# nfc-epd-afe.net
KiCad netlist of a schematic drawn in Altium Designer
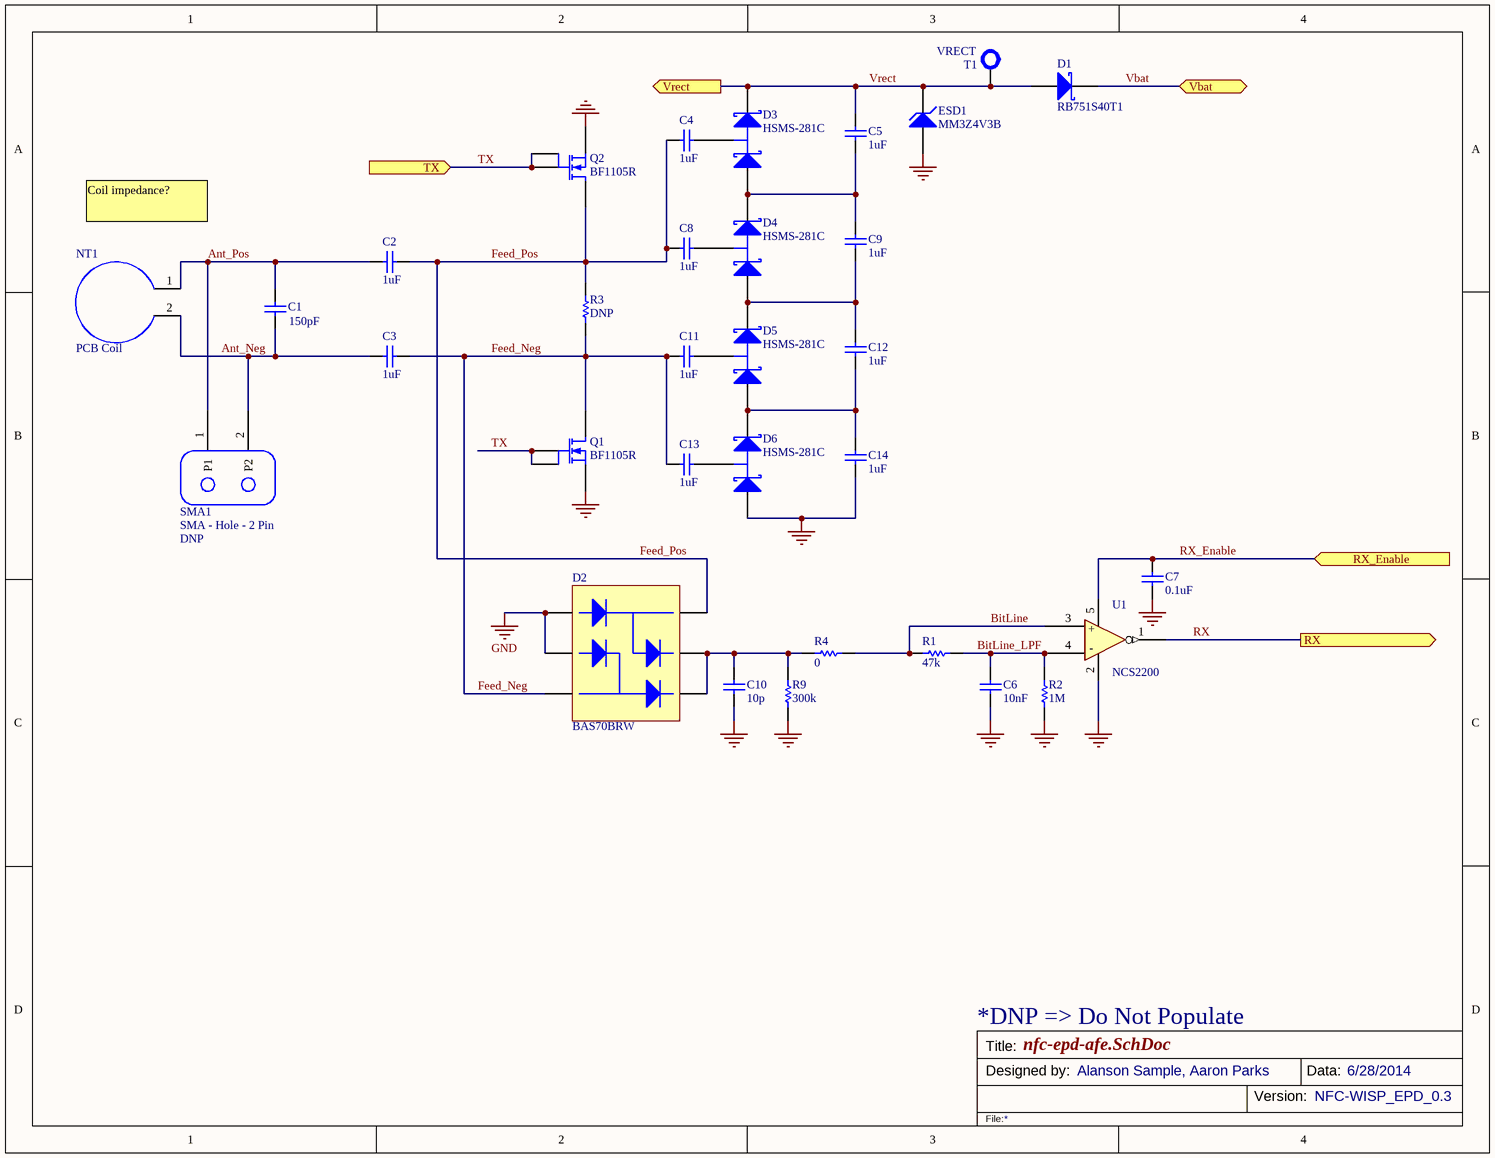
[diagram p0: nfc-epd-afe.SchDoc]

(export (version "E")
  (design (tool "Eeschema 10.0.6"))
  (components
    (comp (ref "C1")
      (value "150pF")
      (footprint "0603")
      (description "Ceramic Capacitor (Surface Mount)")
      (fields (field (name "MANUFACTURER") "Generic Ceramic Chip Cap (TBD)") (field (name "Comment") "Cap"))
      (libsource (lib "WISP_AD10") (part "Cap"))
    )
    (comp (ref "C2")
      (value "1uF")
      (footprint "0402")
      (description "Ceramic Capacitor (Surface Mount)")
      (fields (field (name "MANUFACTURER") "Generic Ceramic Chip Cap (TBD)") (field (name "Comment") "Cap"))
      (libsource (lib "WISP_AD10") (part "Cap"))
    )
    (comp (ref "C3")
      (value "1uF")
      (footprint "0402")
      (description "Ceramic Capacitor (Surface Mount)")
      (fields (field (name "MANUFACTURER") "Generic Ceramic Chip Cap (TBD)") (field (name "Comment") "Cap"))
      (libsource (lib "WISP_AD10") (part "Cap"))
    )
    (comp (ref "C4")
      (value "1uF")
      (footprint "0402")
      (description "Ceramic Capacitor (Surface Mount)")
      (fields (field (name "MANUFACTURER") "Generic Ceramic Chip Cap (TBD)") (field (name "Comment") "Cap"))
      (libsource (lib "WISP_AD10") (part "Cap"))
    )
    (comp (ref "C5")
      (value "1uF")
      (footprint "0402")
      (description "Ceramic Capacitor (Surface Mount)")
      (fields (field (name "MANUFACTURER") "Generic Ceramic Chip Cap (TBD)") (field (name "Comment") "Cap"))
      (libsource (lib "WISP_AD10") (part "Cap"))
    )
    (comp (ref "C6")
      (value "10nF")
      (footprint "0402")
      (description "Ceramic Capacitor (Surface Mount)")
      (fields (field (name "MANUFACTURER") "Generic Ceramic Chip Cap (TBD)") (field (name "Comment") "Cap"))
      (libsource (lib "WISP_AD10") (part "Cap"))
    )
    (comp (ref "C7")
      (value "0.1uF")
      (footprint "0402")
      (description "Ceramic Capacitor (Surface Mount)")
      (fields (field (name "MANUFACTURER") "Generic Ceramic Chip Cap (TBD)") (field (name "Comment") "Cap"))
      (libsource (lib "WISP_AD10") (part "Cap"))
    )
    (comp (ref "C8")
      (value "1uF")
      (footprint "0402")
      (description "Ceramic Capacitor (Surface Mount)")
      (fields (field (name "MANUFACTURER") "Generic Ceramic Chip Cap (TBD)") (field (name "Comment") "Cap"))
      (libsource (lib "WISP_AD10") (part "Cap"))
    )
    (comp (ref "C9")
      (value "1uF")
      (footprint "0402")
      (description "Ceramic Capacitor (Surface Mount)")
      (fields (field (name "MANUFACTURER") "Generic Ceramic Chip Cap (TBD)") (field (name "Comment") "Cap"))
      (libsource (lib "WISP_AD10") (part "Cap"))
    )
    (comp (ref "C10")
      (value "10p")
      (footprint "0402")
      (description "Ceramic Capacitor (Surface Mount)")
      (fields (field (name "MANUFACTURER") "Generic Ceramic Chip Cap (TBD)") (field (name "Comment") "Cap"))
      (libsource (lib "WISP_AD10") (part "Cap"))
    )
    (comp (ref "C11")
      (value "1uF")
      (footprint "0402")
      (description "Ceramic Capacitor (Surface Mount)")
      (fields (field (name "MANUFACTURER") "Generic Ceramic Chip Cap (TBD)") (field (name "Comment") "Cap"))
      (libsource (lib "WISP_AD10") (part "Cap"))
    )
    (comp (ref "C12")
      (value "1uF")
      (footprint "0402")
      (description "Ceramic Capacitor (Surface Mount)")
      (fields (field (name "MANUFACTURER") "Generic Ceramic Chip Cap (TBD)") (field (name "Comment") "Cap"))
      (libsource (lib "WISP_AD10") (part "Cap"))
    )
    (comp (ref "C13")
      (value "1uF")
      (footprint "0402")
      (description "Ceramic Capacitor (Surface Mount)")
      (fields (field (name "MANUFACTURER") "Generic Ceramic Chip Cap (TBD)") (field (name "Comment") "Cap"))
      (libsource (lib "WISP_AD10") (part "Cap"))
    )
    (comp (ref "C14")
      (value "1uF")
      (footprint "0402")
      (description "Ceramic Capacitor (Surface Mount)")
      (fields (field (name "MANUFACTURER") "Generic Ceramic Chip Cap (TBD)") (field (name "Comment") "Cap"))
      (libsource (lib "WISP_AD10") (part "Cap"))
    )
    (comp (ref "D1")
      (value "RB751S40T1")
      (footprint "SOD-523")
      (description "Schottky Diode")
      (fields (field (name "PUBLISHER") "Altium Limited"))
      (libsource (lib "WISP_AD10") (part "RB751S40T1"))
    )
    (comp (ref "D2")
      (value "BAS70BRW")
      (footprint "SOT-363")
      (description "Diode Array - 2 Pair Series Connection")
      (fields
        (field (name "MANUFACTURER") "Diodes Inc")
        (field (name "MANUFACTURER PART NUMBER") "BAS70BRW-7-F")
      )
      (libsource (lib "WISP_AD10") (part "Diode - Array_2"))
    )
    (comp (ref "D3")
      (value "HSMS-281C")
      (footprint "SOT-323, HSMS-285C")
      (description "Agilent Schottky Diode, Two in Series, Small Package SOT-323")
      (fields
        (field (name "DIGI-KEY PART NUMBER") "*not stocked")
        (field (name "MANUFACTURER") "Avago Technologies US Inc.")
      )
      (libsource (lib "WISP_AD10") (part "HSMS-281C"))
    )
    (comp (ref "D4")
      (value "HSMS-281C")
      (footprint "SOT-323, HSMS-285C")
      (description "Agilent Schottky Diode, Two in Series, Small Package SOT-323")
      (fields
        (field (name "DIGI-KEY PART NUMBER") "*not stocked")
        (field (name "MANUFACTURER") "Avago Technologies US Inc.")
      )
      (libsource (lib "WISP_AD10") (part "HSMS-281C"))
    )
    (comp (ref "D5")
      (value "HSMS-281C")
      (footprint "SOT-323, HSMS-285C")
      (description "Agilent Schottky Diode, Two in Series, Small Package SOT-323")
      (fields
        (field (name "DIGI-KEY PART NUMBER") "*not stocked")
        (field (name "MANUFACTURER") "Avago Technologies US Inc.")
      )
      (libsource (lib "WISP_AD10") (part "HSMS-281C"))
    )
    (comp (ref "D6")
      (value "HSMS-281C")
      (footprint "SOT-323, HSMS-285C")
      (description "Agilent Schottky Diode, Two in Series, Small Package SOT-323")
      (fields
        (field (name "DIGI-KEY PART NUMBER") "*not stocked")
        (field (name "MANUFACTURER") "Avago Technologies US Inc.")
      )
      (libsource (lib "WISP_AD10") (part "HSMS-281C"))
    )
    (comp (ref "ESD1")
      (value "MM3Z4V3B")
      (footprint "SOD-323")
      (description "Vz=4.3V, Overvoltage Protection Zener")
      (fields (field (name "MANUFACTURER") "Fairchild") (field (name "DIGI-KEY PART NUMBER") "MM3Z4V3BCT-ND"))
      (libsource (lib "WISP_AD10") (part "MM3Z4V3B"))
    )
    (comp (ref "NT1")
      (value "PCB Coil")
      (footprint "Net Tie - 20mil")
      (description "Hand draw coil symbol based on a 'Net Tie'")
      (libsource (lib "WISP_AD10") (part "Net Tie - Coil"))
    )
    (comp (ref "Q1")
      (value "BF1105R")
      (footprint "SOT-143R")
      (description "SOT-143R, N-Channel Dual-Gate Mos-Fets MOSFET")
      (fields
        (field (name "DIGI-KEY PART NUMBER") "BF1105R,215-ND")
        (field (name "MANUFACTURER PART NUMBER") "BF1105R,215")
      )
      (libsource (lib "WISP_AD10") (part "BF1105R"))
    )
    (comp (ref "Q2")
      (value "BF1105R")
      (footprint "SOT-143R")
      (description "SOT-143R, N-Channel Dual-Gate Mos-Fets MOSFET")
      (fields
        (field (name "DIGI-KEY PART NUMBER") "BF1105R,215-ND")
        (field (name "MANUFACTURER PART NUMBER") "BF1105R,215")
      )
      (libsource (lib "WISP_AD10") (part "BF1105R"))
    )
    (comp (ref "R1")
      (value "47k")
      (footprint "0402")
      (description "Chip Resistor (Surface Mount)")
      (fields (field (name "MANUFACTURER") "Generic Chip Res (TBD)") (field (name "Comment") "Res"))
      (libsource (lib "WISP_AD10") (part "Res"))
    )
    (comp (ref "R2")
      (value "1M")
      (footprint "0402")
      (description "Chip Resistor (Surface Mount)")
      (fields (field (name "MANUFACTURER") "Generic Chip Res (TBD)") (field (name "Comment") "Res"))
      (libsource (lib "WISP_AD10") (part "Res"))
    )
    (comp (ref "R3")
      (value "DNP")
      (footprint "0402")
      (description "Chip Resistor (Surface Mount)")
      (fields (field (name "MANUFACTURER") "Generic Chip Res (TBD)") (field (name "Comment") "Res"))
      (libsource (lib "WISP_AD10") (part "Res"))
    )
    (comp (ref "R4")
      (value "0")
      (footprint "0402")
      (description "Chip Resistor (Surface Mount)")
      (fields (field (name "MANUFACTURER") "Generic Chip Res (TBD)") (field (name "Comment") "Res"))
      (libsource (lib "WISP_AD10") (part "Res"))
    )
    (comp (ref "R9")
      (value "300k")
      (footprint "0402")
      (description "Chip Resistor (Surface Mount)")
      (fields (field (name "MANUFACTURER") "Generic Chip Res (TBD)") (field (name "Comment") "Res"))
      (libsource (lib "WISP_AD10") (part "Res"))
    )
    (comp (ref "SMA1")
      (value "SMA - Hole - 2 Pin")
      (footprint "SMA - Hole - 2 Pin")
      (description "Two pin SMA connector wisp")
      (fields (field (name "NOTE") "DNP"))
      (libsource (lib "WISP_AD10") (part "SMA - Hole - 2 Pin"))
    )
    (comp (ref "T1")
      (value "Test Point")
      (footprint "Test Point - Super Small")
      (description "Test Point, large or small foot prints")
      (fields
        (field (name "DIGI-KEY PART NUMBER") "Example: 5000K-ND, 5012K-ND, Surface mount 5015KCT-ND")
        (field (name "MANUFACTURER PART NUMBER") "Example: 5000, 5013")
        (field (name "NOTE") "VRECT")
      )
      (libsource (lib "WISP_AD10") (part "Test Point"))
    )
    (comp (ref "U1")
      (value "NCS2200")
      (footprint "SC70-5")
      (description "Comparator: On Semi 10uA Comparator")
      (fields
        (field (name "DIGI-KEY PART NUMBER") "NCS2200SQ2T2GOSTR-ND")
        (field (name "MANUFACTURER") "ON Semiconductor")
      )
      (libsource (lib "WISP_AD10") (part "NCS2200"))
    )
  )
  (nets
    (net (code "1") (name "/Ant_Neg") (class "Default")
      (node (ref "C1") (pin "2") (pinfunction "2_2") (pintype "passive"))
      (node (ref "C3") (pin "1") (pinfunction "1_1") (pintype "passive"))
      (node (ref "NT1") (pin "2") (pinfunction "N2_2") (pintype "passive"))
      (node (ref "SMA1") (pin "2") (pinfunction "P2_2") (pintype "passive"))
    )
    (net (code "2") (name "/Ant_Pos") (class "Default")
      (node (ref "C1") (pin "1") (pinfunction "1_1") (pintype "passive"))
      (node (ref "C2") (pin "1") (pinfunction "1_1") (pintype "passive"))
      (node (ref "NT1") (pin "1") (pinfunction "N1_1") (pintype "passive"))
      (node (ref "SMA1") (pin "1") (pinfunction "P1_1") (pintype "passive"))
    )
    (net (code "3") (name "/BitLine") (class "Default")
      (node (ref "R1") (pin "1") (pinfunction "1_1") (pintype "passive"))
      (node (ref "R4") (pin "2") (pinfunction "2_2") (pintype "passive"))
      (node (ref "U1") (pin "3") (pinfunction "IN+_3") (pintype "passive"))
    )
    (net (code "4") (name "/BitLine_LPF") (class "Default")
      (node (ref "C6") (pin "1") (pinfunction "1_1") (pintype "passive"))
      (node (ref "R1") (pin "2") (pinfunction "2_2") (pintype "passive"))
      (node (ref "R2") (pin "1") (pinfunction "1_1") (pintype "passive"))
      (node (ref "U1") (pin "4") (pinfunction "In-_4") (pintype "passive"))
    )
    (net (code "5") (name "/Feed_Neg") (class "Default")
      (node (ref "C11") (pin "1") (pinfunction "1_1") (pintype "passive"))
      (node (ref "C13") (pin "1") (pinfunction "1_1") (pintype "passive"))
      (node (ref "C3") (pin "2") (pinfunction "2_2") (pintype "passive"))
      (node (ref "D2") (pin "3") (pinfunction "AC2_3") (pintype "passive"))
      (node (ref "Q1") (pin "2") (pinfunction "D_2") (pintype "passive"))
      (node (ref "R3") (pin "2") (pinfunction "2_2") (pintype "passive"))
    )
    (net (code "6") (name "/Feed_Pos") (class "Default")
      (node (ref "C2") (pin "2") (pinfunction "2_2") (pintype "passive"))
      (node (ref "C4") (pin "1") (pinfunction "1_1") (pintype "passive"))
      (node (ref "C8") (pin "1") (pinfunction "1_1") (pintype "passive"))
      (node (ref "D2") (pin "6") (pinfunction "AC1_6") (pintype "passive"))
      (node (ref "Q2") (pin "2") (pinfunction "D_2") (pintype "passive"))
      (node (ref "R3") (pin "1") (pinfunction "1_1") (pintype "passive"))
    )
    (net (code "7") (name "/RX") (class "Default")
      (node (ref "U1") (pin "1") (pinfunction "OUT_1") (pintype "output"))
    )
    (net (code "8") (name "/RX_Enable") (class "Default")
      (node (ref "C7") (pin "1") (pinfunction "1_1") (pintype "passive"))
      (node (ref "U1") (pin "5") (pinfunction "VDD_5") (pintype "passive"))
    )
    (net (code "9") (name "/TX") (class "Default")
      (node (ref "Q1") (pin "3") (pinfunction "G_3") (pintype "passive"))
      (node (ref "Q1") (pin "4") (pinfunction "G_4") (pintype "passive"))
      (node (ref "Q2") (pin "3") (pinfunction "G_3") (pintype "passive"))
      (node (ref "Q2") (pin "4") (pinfunction "G_4") (pintype "passive"))
    )
    (net (code "10") (name "/Vbat") (class "Default")
      (node (ref "D1") (pin "2") (pinfunction "C_2") (pintype "passive"))
    )
    (net (code "11") (name "/Vrect") (class "Default")
      (node (ref "C5") (pin "2") (pinfunction "2_2") (pintype "passive"))
      (node (ref "D1") (pin "1") (pinfunction "A_1") (pintype "passive"))
      (node (ref "D3") (pin "2") (pinfunction "K_2") (pintype "passive"))
      (node (ref "ESD1") (pin "2") (pinfunction "C_2") (pintype "passive"))
      (node (ref "T1") (pin "0") (pinfunction "0_0") (pintype "passive"))
    )
    (net (code "12") (name "GND") (class "Default")
      (node (ref "C10") (pin "2") (pinfunction "2_2") (pintype "passive"))
      (node (ref "C14") (pin "1") (pinfunction "1_1") (pintype "passive"))
      (node (ref "C6") (pin "2") (pinfunction "2_2") (pintype "passive"))
      (node (ref "C7") (pin "2") (pinfunction "2_2") (pintype "passive"))
      (node (ref "D2") (pin "1") (pinfunction "A1_1") (pintype "passive"))
      (node (ref "D2") (pin "2") (pinfunction "A2_2") (pintype "passive"))
      (node (ref "D6") (pin "1") (pinfunction "A_1") (pintype "passive"))
      (node (ref "ESD1") (pin "1") (pinfunction "A_1") (pintype "passive"))
      (node (ref "Q1") (pin "1") (pinfunction "S_1") (pintype "passive"))
      (node (ref "Q2") (pin "1") (pinfunction "S_1") (pintype "passive"))
      (node (ref "R2") (pin "2") (pinfunction "2_2") (pintype "passive"))
      (node (ref "R9") (pin "2") (pinfunction "2_2") (pintype "passive"))
      (node (ref "U1") (pin "2") (pinfunction "Gnd_2") (pintype "power_in"))
    )
    (net (code "13") (name "Net-(D2-C1)") (class "Default")
      (node (ref "C10") (pin "1") (pinfunction "1_1") (pintype "passive"))
      (node (ref "D2") (pin "4") (pinfunction "C2_4") (pintype "passive"))
      (node (ref "D2") (pin "5") (pinfunction "C1_5") (pintype "passive"))
      (node (ref "R4") (pin "1") (pinfunction "1_1") (pintype "passive"))
      (node (ref "R9") (pin "1") (pinfunction "1_1") (pintype "passive"))
    )
    (net (code "14") (name "Net-(D3-A)") (class "Default")
      (node (ref "C5") (pin "1") (pinfunction "1_1") (pintype "passive"))
      (node (ref "C9") (pin "2") (pinfunction "2_2") (pintype "passive"))
      (node (ref "D3") (pin "1") (pinfunction "A_1") (pintype "passive"))
      (node (ref "D4") (pin "2") (pinfunction "K_2") (pintype "passive"))
    )
    (net (code "15") (name "Net-(D3-C)") (class "Default")
      (node (ref "C4") (pin "2") (pinfunction "2_2") (pintype "passive"))
      (node (ref "D3") (pin "3") (pinfunction "C_3") (pintype "passive"))
    )
    (net (code "16") (name "Net-(D4-A)") (class "Default")
      (node (ref "C12") (pin "2") (pinfunction "2_2") (pintype "passive"))
      (node (ref "C9") (pin "1") (pinfunction "1_1") (pintype "passive"))
      (node (ref "D4") (pin "1") (pinfunction "A_1") (pintype "passive"))
      (node (ref "D5") (pin "2") (pinfunction "K_2") (pintype "passive"))
    )
    (net (code "17") (name "Net-(D4-C)") (class "Default")
      (node (ref "C8") (pin "2") (pinfunction "2_2") (pintype "passive"))
      (node (ref "D4") (pin "3") (pinfunction "C_3") (pintype "passive"))
    )
    (net (code "18") (name "Net-(D5-A)") (class "Default")
      (node (ref "C12") (pin "1") (pinfunction "1_1") (pintype "passive"))
      (node (ref "C14") (pin "2") (pinfunction "2_2") (pintype "passive"))
      (node (ref "D5") (pin "1") (pinfunction "A_1") (pintype "passive"))
      (node (ref "D6") (pin "2") (pinfunction "K_2") (pintype "passive"))
    )
    (net (code "19") (name "Net-(D5-C)") (class "Default")
      (node (ref "C11") (pin "2") (pinfunction "2_2") (pintype "passive"))
      (node (ref "D5") (pin "3") (pinfunction "C_3") (pintype "passive"))
    )
    (net (code "20") (name "Net-(D6-C)") (class "Default")
      (node (ref "C13") (pin "2") (pinfunction "2_2") (pintype "passive"))
      (node (ref "D6") (pin "3") (pinfunction "C_3") (pintype "passive"))
    )
  )
)
